# Controller_Sheet.net
KiCad netlist of a schematic drawn in Altium Designer
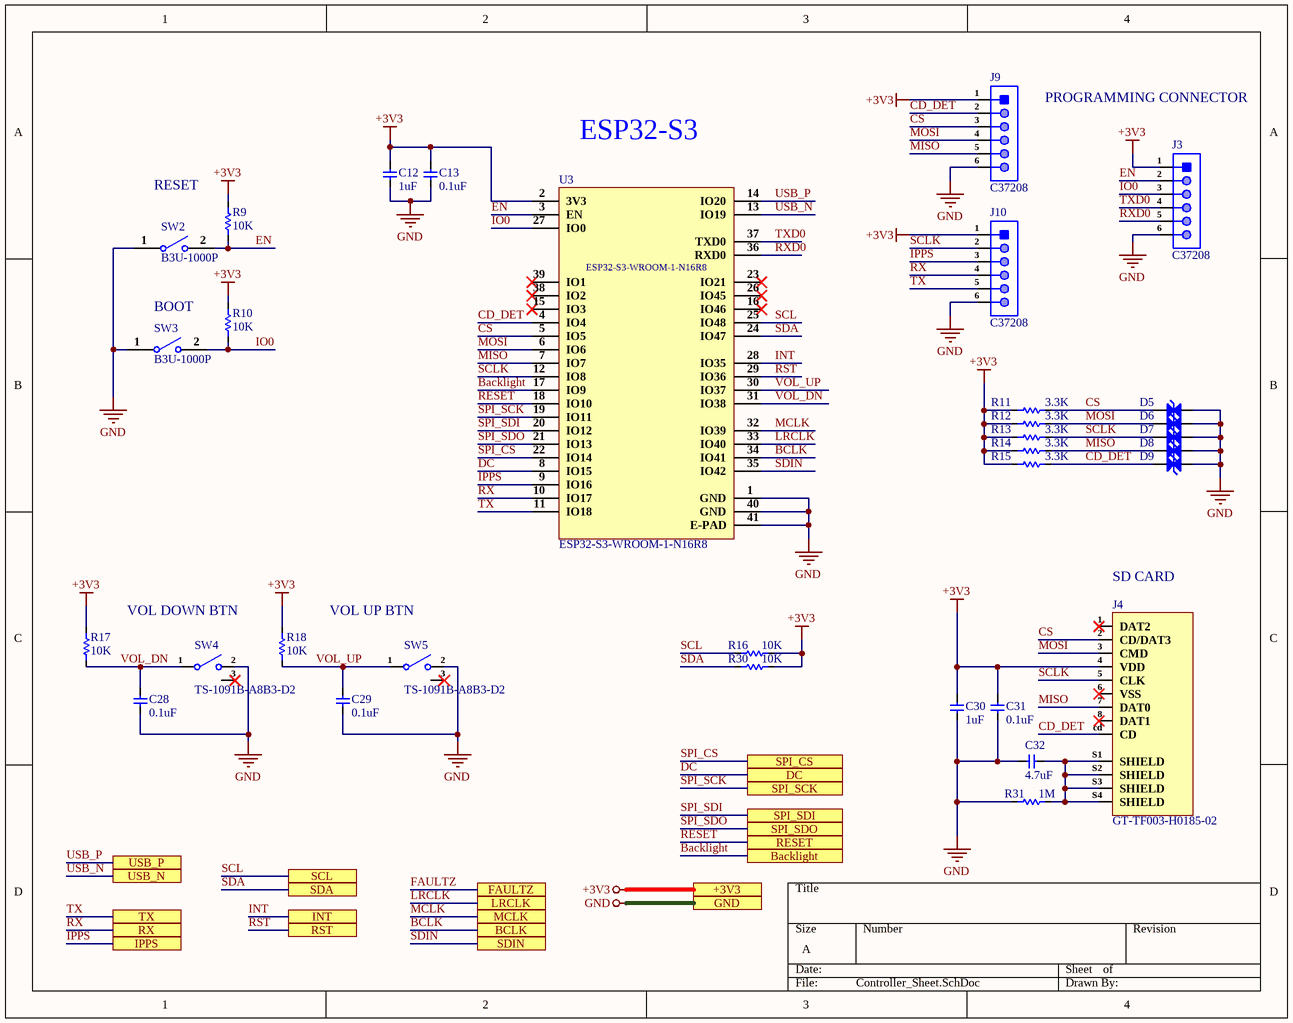
[diagram p0: Controller_Sheet.SchDoc]

(export (version "E")
  (design (tool "Eeschema 10.0.6"))
  (components
    (comp (ref "C12")
      (value "1uF")
      (footprint "Cap-0603")
      (description "CAP CER 1UF 25V X5R 0603")
      (fields
        (field (name "MANUFACTURER") "Yageo")
        (field (name "MANUFACTURER PART NUMBER") "CC0603KRX5R8BB105")
      )
      (libsource (lib "DigitalAzanClock") (part "CC0603KRX5R8BB105"))
    )
    (comp (ref "C13")
      (value "0.1uF")
      (footprint "Cap-0603")
      (description "CAP CER 0.1UF 100V X7R 0603")
      (fields
        (field (name "MANUFACTURER") "Yageo")
        (field (name "MANUFACTURER PART NUMBER") "CC0603KRX7R0BB104")
      )
      (libsource (lib "DigitalAzanClock") (part "CC0603KRX7R0BB104"))
    )
    (comp (ref "C28")
      (value "0.1uF")
      (footprint "Cap-0603")
      (description "CAP CER 0.1UF 100V X7R 0603")
      (fields
        (field (name "MANUFACTURER") "Yageo")
        (field (name "MANUFACTURER PART NUMBER") "CC0603KRX7R0BB104")
      )
      (libsource (lib "DigitalAzanClock") (part "CC0603KRX7R0BB104"))
    )
    (comp (ref "C29")
      (value "0.1uF")
      (footprint "Cap-0603")
      (description "CAP CER 0.1UF 100V X7R 0603")
      (fields
        (field (name "MANUFACTURER") "Yageo")
        (field (name "MANUFACTURER PART NUMBER") "CC0603KRX7R0BB104")
      )
      (libsource (lib "DigitalAzanClock") (part "CC0603KRX7R0BB104"))
    )
    (comp (ref "C30")
      (value "1uF")
      (footprint "Cap-0603")
      (description "CAP CER 1UF 25V X5R 0603")
      (fields
        (field (name "MANUFACTURER") "Yageo")
        (field (name "MANUFACTURER PART NUMBER") "CC0603KRX5R8BB105")
      )
      (libsource (lib "DigitalAzanClock") (part "CC0603KRX5R8BB105"))
    )
    (comp (ref "C31")
      (value "0.1uF")
      (footprint "Cap-0603")
      (description "CAP CER 0.1UF 100V X7R 0603")
      (fields
        (field (name "MANUFACTURER") "Yageo")
        (field (name "MANUFACTURER PART NUMBER") "CC0603KRX7R0BB104")
      )
      (libsource (lib "DigitalAzanClock") (part "CC0603KRX7R0BB104"))
    )
    (comp (ref "C32")
      (value "4.7uF")
      (footprint "Cap-0603")
      (description "50V 4.7nF X7R ±10% 0603 Multilayer Ceramic Capacitors MLCC - SMD/SMT ROHS")
      (fields
        (field (name "MANUFACTURER") "YAGEO")
        (field (name "MANUFACTURER PART NUMBER") "CC0603KRX7R9BB472")
      )
      (libsource (lib "DigitalAzanClock") (part "CC0603KRX7R9BB472"))
    )
    (comp (ref "D5")
      (value "ESD9X5VU")
      (footprint "DFN1006-2L_")
      (description "DFN1006-2 ESD Protection Devices ROHS")
      (fields (field (name "MANUFACTURER") "TECH PUBLIC") (field (name "LCSC PART NUMBER") "C2875160"))
      (libsource (lib "DigitalAzanClock") (part "ESD9X5VU"))
    )
    (comp (ref "D6")
      (value "ESD9X5VU")
      (footprint "DFN1006-2L_")
      (description "DFN1006-2 ESD Protection Devices ROHS")
      (fields (field (name "MANUFACTURER") "TECH PUBLIC") (field (name "LCSC PART NUMBER") "C2875160"))
      (libsource (lib "DigitalAzanClock") (part "ESD9X5VU"))
    )
    (comp (ref "D7")
      (value "ESD9X5VU")
      (footprint "DFN1006-2L_")
      (description "DFN1006-2 ESD Protection Devices ROHS")
      (fields (field (name "MANUFACTURER") "TECH PUBLIC") (field (name "LCSC PART NUMBER") "C2875160"))
      (libsource (lib "DigitalAzanClock") (part "ESD9X5VU"))
    )
    (comp (ref "D8")
      (value "ESD9X5VU")
      (footprint "DFN1006-2L_")
      (description "DFN1006-2 ESD Protection Devices ROHS")
      (fields (field (name "MANUFACTURER") "TECH PUBLIC") (field (name "LCSC PART NUMBER") "C2875160"))
      (libsource (lib "DigitalAzanClock") (part "ESD9X5VU"))
    )
    (comp (ref "D9")
      (value "ESD9X5VU")
      (footprint "DFN1006-2L_")
      (description "DFN1006-2 ESD Protection Devices ROHS")
      (fields (field (name "MANUFACTURER") "TECH PUBLIC") (field (name "LCSC PART NUMBER") "C2875160"))
      (libsource (lib "DigitalAzanClock") (part "ESD9X5VU"))
    )
    (comp (ref "J3")
      (value "C37208")
      (footprint "HDR1X6_")
      (description "Straight 1 6 2.54mm Black Brass Plugin,P=2.54mm Pin Headers ROHS")
      (fields (field (name "MANUFACTURER") "BOOMELEC"))
      (libsource (lib "DigitalAzanClock") (part "C37208"))
    )
    (comp (ref "J4")
      (value "GT-TF003-H0185-02")
      (footprint "GT-TF003-H0185-02")
      (fields (field (name "MANUFACTURER") "G-Switch") (field (name "LCSC PART NUMBER") "C5155564"))
      (libsource (lib "DigitalAzanClock") (part "GT-TF003-H0185-02"))
    )
    (comp (ref "J9")
      (value "C37208")
      (footprint "HDR1X6_")
      (description "Straight 1 6 2.54mm Black Brass Plugin,P=2.54mm Pin Headers ROHS")
      (fields (field (name "MANUFACTURER") "BOOMELEC"))
      (libsource (lib "DigitalAzanClock") (part "C37208"))
    )
    (comp (ref "J10")
      (value "C37208")
      (footprint "HDR1X6_")
      (description "Straight 1 6 2.54mm Black Brass Plugin,P=2.54mm Pin Headers ROHS")
      (fields (field (name "MANUFACTURER") "BOOMELEC"))
      (libsource (lib "DigitalAzanClock") (part "C37208"))
    )
    (comp (ref "R9")
      (value "10K")
      (footprint "Res-0603")
      (description "RES SMD 10K OHM 0.1% 1/10W 0603")
      (fields
        (field (name "MANUFACTURER") "Yageo")
        (field (name "MANUFACTURER PART NUMBER") "RT0603BRD0710KL")
      )
      (libsource (lib "DigitalAzanClock") (part "RT0603BRD0710KL"))
    )
    (comp (ref "R10")
      (value "10K")
      (footprint "Res-0603")
      (description "RES SMD 10K OHM 0.1% 1/10W 0603")
      (fields
        (field (name "MANUFACTURER") "Yageo")
        (field (name "MANUFACTURER PART NUMBER") "RT0603BRD0710KL")
      )
      (libsource (lib "DigitalAzanClock") (part "RT0603BRD0710KL"))
    )
    (comp (ref "R11")
      (value "3.3K")
      (footprint "Res-0603")
      (description "100mW Thick Film Resistors 75V ±100ppm/℃ ±1% 3.3kΩ 0603 Chip Resistor - Surface Mount ROHS")
      (fields
        (field (name "MANUFACTURER") "UNI-ROYAL(Uniroyal Elec)")
        (field (name "MANUFACTURER PART NUMBER") "0603WAF3301T5E")
      )
      (libsource (lib "DigitalAzanClock") (part "0603WAF3301T5E"))
    )
    (comp (ref "R12")
      (value "3.3K")
      (footprint "Res-0603")
      (description "100mW Thick Film Resistors 75V ±100ppm/℃ ±1% 3.3kΩ 0603 Chip Resistor - Surface Mount ROHS")
      (fields
        (field (name "MANUFACTURER") "UNI-ROYAL(Uniroyal Elec)")
        (field (name "MANUFACTURER PART NUMBER") "0603WAF3301T5E")
      )
      (libsource (lib "DigitalAzanClock") (part "0603WAF3301T5E"))
    )
    (comp (ref "R13")
      (value "3.3K")
      (footprint "Res-0603")
      (description "100mW Thick Film Resistors 75V ±100ppm/℃ ±1% 3.3kΩ 0603 Chip Resistor - Surface Mount ROHS")
      (fields
        (field (name "MANUFACTURER") "UNI-ROYAL(Uniroyal Elec)")
        (field (name "MANUFACTURER PART NUMBER") "0603WAF3301T5E")
      )
      (libsource (lib "DigitalAzanClock") (part "0603WAF3301T5E"))
    )
    (comp (ref "R14")
      (value "3.3K")
      (footprint "Res-0603")
      (description "100mW Thick Film Resistors 75V ±100ppm/℃ ±1% 3.3kΩ 0603 Chip Resistor - Surface Mount ROHS")
      (fields
        (field (name "MANUFACTURER") "UNI-ROYAL(Uniroyal Elec)")
        (field (name "MANUFACTURER PART NUMBER") "0603WAF3301T5E")
      )
      (libsource (lib "DigitalAzanClock") (part "0603WAF3301T5E"))
    )
    (comp (ref "R15")
      (value "3.3K")
      (footprint "Res-0603")
      (description "100mW Thick Film Resistors 75V ±100ppm/℃ ±1% 3.3kΩ 0603 Chip Resistor - Surface Mount ROHS")
      (fields
        (field (name "MANUFACTURER") "UNI-ROYAL(Uniroyal Elec)")
        (field (name "MANUFACTURER PART NUMBER") "0603WAF3301T5E")
      )
      (libsource (lib "DigitalAzanClock") (part "0603WAF3301T5E"))
    )
    (comp (ref "R16")
      (value "10K")
      (footprint "Res-0603")
      (description "RES SMD 10K OHM 0.1% 1/10W 0603")
      (fields
        (field (name "MANUFACTURER") "Yageo")
        (field (name "MANUFACTURER PART NUMBER") "RT0603BRD0710KL")
      )
      (libsource (lib "DigitalAzanClock") (part "RT0603BRD0710KL"))
    )
    (comp (ref "R17")
      (value "10K")
      (footprint "Res-0603")
      (description "RES SMD 10K OHM 0.1% 1/10W 0603")
      (fields
        (field (name "MANUFACTURER") "Yageo")
        (field (name "MANUFACTURER PART NUMBER") "RT0603BRD0710KL")
      )
      (libsource (lib "DigitalAzanClock") (part "RT0603BRD0710KL"))
    )
    (comp (ref "R18")
      (value "10K")
      (footprint "Res-0603")
      (description "RES SMD 10K OHM 0.1% 1/10W 0603")
      (fields
        (field (name "MANUFACTURER") "Yageo")
        (field (name "MANUFACTURER PART NUMBER") "RT0603BRD0710KL")
      )
      (libsource (lib "DigitalAzanClock") (part "RT0603BRD0710KL"))
    )
    (comp (ref "R30")
      (value "10K")
      (footprint "Res-0603")
      (description "RES SMD 10K OHM 0.1% 1/10W 0603")
      (fields
        (field (name "MANUFACTURER") "Yageo")
        (field (name "MANUFACTURER PART NUMBER") "RT0603BRD0710KL")
      )
      (libsource (lib "DigitalAzanClock") (part "RT0603BRD0710KL"))
    )
    (comp (ref "R31")
      (value "1M")
      (footprint "Res-0402")
      (description "RES SMD 1M OHM 5% 1/16W 0402")
      (fields
        (field (name "MANUFACTURER") "Yageo")
        (field (name "MANUFACTURER PART NUMBER") "AF0402JR-071ML")
      )
      (libsource (lib "DigitalAzanClock") (part "AF0402JR-071ML"))
    )
    (comp (ref "SW2")
      (value "B3U-1000P")
      (footprint "B3U-1000P")
      (description "SWITCH TACTILE SPST-NO 0.05A 12V")
      (fields (field (name "MANUFACTURER") "Omron") (field (name "LCSC PART NUMBER") "C231329"))
      (libsource (lib "DigitalAzanClock") (part "B3U-1000P"))
    )
    (comp (ref "SW3")
      (value "B3U-1000P")
      (footprint "B3U-1000P")
      (description "SWITCH TACTILE SPST-NO 0.05A 12V")
      (fields (field (name "MANUFACTURER") "Omron") (field (name "LCSC PART NUMBER") "C231329"))
      (libsource (lib "DigitalAzanClock") (part "B3U-1000P"))
    )
    (comp (ref "SW4")
      (value "TS-1091B-A8B3-D2")
      (footprint "TS-1091B-A8B3-D2")
      (description "NO Lying SPST 250gf@±30gf Plugin Tactile Switches ROHS")
      (fields (field (name "MANUFACTURER") "Yuandi") (field (name "LCSC PART NUMBER") "C557914"))
      (libsource (lib "DigitalAzanClock") (part "TS-1091B-A8B3-D2"))
    )
    (comp (ref "SW5")
      (value "TS-1091B-A8B3-D2")
      (footprint "TS-1091B-A8B3-D2")
      (description "NO Lying SPST 250gf@±30gf Plugin Tactile Switches ROHS")
      (fields (field (name "MANUFACTURER") "Yuandi") (field (name "LCSC PART NUMBER") "C557914"))
      (libsource (lib "DigitalAzanClock") (part "TS-1091B-A8B3-D2"))
    )
    (comp (ref "U3")
      (value "ESP32-S3-WROOM-1-N16R8")
      (footprint "41-SMD Module")
      (description "ESP32-S3 chip 2.4GHz SMD,18x25.5mm WiFi Modules ROHS")
      (fields
        (field (name "MANUFACTURER") "Expressif System")
        (field (name "MANUFACTURER PART NUMBER") "ESP32-S3-WROOM-1-N8")
      )
      (libsource (lib "DigitalAzanClock") (part "ESP32-S3-WROOM-1-N16R8"))
    )
  )
  (nets
    (net (code "1") (name "+3V3") (class "Default")
      (node (ref "C12") (pin "2") (pinfunction "2_2") (pintype "passive"))
      (node (ref "C13") (pin "2") (pinfunction "2_2") (pintype "passive"))
      (node (ref "C30") (pin "2") (pinfunction "2_2") (pintype "passive"))
      (node (ref "C31") (pin "2") (pinfunction "2_2") (pintype "passive"))
      (node (ref "J10") (pin "1") (pinfunction "1_1") (pintype "passive"))
      (node (ref "J3") (pin "1") (pinfunction "1_1") (pintype "passive"))
      (node (ref "J4") (pin "4") (pinfunction "VDD_4") (pintype "passive"))
      (node (ref "J9") (pin "1") (pinfunction "1_1") (pintype "passive"))
      (node (ref "R10") (pin "2") (pinfunction "2_2") (pintype "passive"))
      (node (ref "R11") (pin "1") (pinfunction "1_1") (pintype "passive"))
      (node (ref "R12") (pin "1") (pinfunction "1_1") (pintype "passive"))
      (node (ref "R13") (pin "1") (pinfunction "1_1") (pintype "passive"))
      (node (ref "R14") (pin "1") (pinfunction "1_1") (pintype "passive"))
      (node (ref "R15") (pin "1") (pinfunction "1_1") (pintype "passive"))
      (node (ref "R16") (pin "1") (pinfunction "1_1") (pintype "passive"))
      (node (ref "R17") (pin "2") (pinfunction "2_2") (pintype "passive"))
      (node (ref "R18") (pin "2") (pinfunction "2_2") (pintype "passive"))
      (node (ref "R30") (pin "1") (pinfunction "1_1") (pintype "passive"))
      (node (ref "R9") (pin "2") (pinfunction "2_2") (pintype "passive"))
      (node (ref "U3") (pin "2") (pinfunction "3V3_2") (pintype "passive"))
    )
    (net (code "2") (name "/BCLK") (class "Default")
      (node (ref "U3") (pin "34") (pinfunction "IO41_34") (pintype "passive"))
    )
    (net (code "3") (name "/Backlight") (class "Default")
      (node (ref "U3") (pin "17") (pinfunction "IO9_17") (pintype "passive"))
    )
    (net (code "4") (name "/CD_DET") (class "Default")
      (node (ref "D9") (pin "1") (pinfunction "A_1") (pintype "passive"))
      (node (ref "J4") (pin "cd") (pinfunction "CD_cd") (pintype "passive"))
      (node (ref "J9") (pin "2") (pinfunction "2_2") (pintype "passive"))
      (node (ref "R15") (pin "2") (pinfunction "2_2") (pintype "passive"))
      (node (ref "U3") (pin "4") (pinfunction "IO4_4") (pintype "passive"))
    )
    (net (code "5") (name "/CS") (class "Default")
      (node (ref "D5") (pin "1") (pinfunction "A_1") (pintype "passive"))
      (node (ref "J4") (pin "2") (pinfunction "CD/DAT3_2") (pintype "passive"))
      (node (ref "J9") (pin "3") (pinfunction "3_3") (pintype "passive"))
      (node (ref "R11") (pin "2") (pinfunction "2_2") (pintype "passive"))
      (node (ref "U3") (pin "5") (pinfunction "IO5_5") (pintype "passive"))
    )
    (net (code "6") (name "/DC") (class "Default")
      (node (ref "U3") (pin "8") (pinfunction "IO15_8") (pintype "passive"))
    )
    (net (code "7") (name "/EN") (class "Default")
      (node (ref "J3") (pin "2") (pinfunction "2_2") (pintype "passive"))
      (node (ref "R9") (pin "1") (pinfunction "1_1") (pintype "passive"))
      (node (ref "SW2") (pin "2") (pinfunction "2_2") (pintype "passive"))
      (node (ref "U3") (pin "3") (pinfunction "EN_3") (pintype "passive"))
    )
    (net (code "9") (name "/INT") (class "Default")
      (node (ref "U3") (pin "28") (pinfunction "IO35_28") (pintype "passive"))
    )
    (net (code "10") (name "/IO0") (class "Default")
      (node (ref "J3") (pin "3") (pinfunction "3_3") (pintype "passive"))
      (node (ref "R10") (pin "1") (pinfunction "1_1") (pintype "passive"))
      (node (ref "SW3") (pin "2") (pinfunction "2_2") (pintype "passive"))
      (node (ref "U3") (pin "27") (pinfunction "IO0_27") (pintype "passive"))
    )
    (net (code "11") (name "/IPPS") (class "Default")
      (node (ref "J10") (pin "3") (pinfunction "3_3") (pintype "passive"))
      (node (ref "U3") (pin "9") (pinfunction "IO16_9") (pintype "passive"))
    )
    (net (code "12") (name "/LRCLK") (class "Default")
      (node (ref "U3") (pin "33") (pinfunction "IO40_33") (pintype "passive"))
    )
    (net (code "13") (name "/MCLK") (class "Default")
      (node (ref "U3") (pin "32") (pinfunction "IO39_32") (pintype "passive"))
    )
    (net (code "14") (name "/MISO") (class "Default")
      (node (ref "D8") (pin "1") (pinfunction "A_1") (pintype "passive"))
      (node (ref "J4") (pin "7") (pinfunction "DAT0_7") (pintype "passive"))
      (node (ref "J9") (pin "5") (pinfunction "5_5") (pintype "passive"))
      (node (ref "R14") (pin "2") (pinfunction "2_2") (pintype "passive"))
      (node (ref "U3") (pin "7") (pinfunction "IO7_7") (pintype "passive"))
    )
    (net (code "15") (name "/MOSI") (class "Default")
      (node (ref "D6") (pin "1") (pinfunction "A_1") (pintype "passive"))
      (node (ref "J4") (pin "3") (pinfunction "CMD_3") (pintype "passive"))
      (node (ref "J9") (pin "4") (pinfunction "4_4") (pintype "passive"))
      (node (ref "R12") (pin "2") (pinfunction "2_2") (pintype "passive"))
      (node (ref "U3") (pin "6") (pinfunction "IO6_6") (pintype "passive"))
    )
    (net (code "16") (name "/RESET") (class "Default")
      (node (ref "U3") (pin "18") (pinfunction "IO10_18") (pintype "passive"))
    )
    (net (code "17") (name "/RST") (class "Default")
      (node (ref "U3") (pin "29") (pinfunction "IO36_29") (pintype "passive"))
    )
    (net (code "18") (name "/RX") (class "Default")
      (node (ref "J10") (pin "4") (pinfunction "4_4") (pintype "passive"))
      (node (ref "U3") (pin "10") (pinfunction "IO17_10") (pintype "passive"))
    )
    (net (code "19") (name "/RXD0") (class "Default")
      (node (ref "J3") (pin "5") (pinfunction "5_5") (pintype "passive"))
      (node (ref "U3") (pin "36") (pinfunction "RXD0_36") (pintype "passive"))
    )
    (net (code "20") (name "/SCL") (class "Default")
      (node (ref "R16") (pin "2") (pinfunction "2_2") (pintype "passive"))
      (node (ref "U3") (pin "25") (pinfunction "IO48_25") (pintype "passive"))
    )
    (net (code "21") (name "/SCLK") (class "Default")
      (node (ref "D7") (pin "1") (pinfunction "A_1") (pintype "passive"))
      (node (ref "J10") (pin "2") (pinfunction "2_2") (pintype "passive"))
      (node (ref "J4") (pin "5") (pinfunction "CLK_5") (pintype "passive"))
      (node (ref "R13") (pin "2") (pinfunction "2_2") (pintype "passive"))
      (node (ref "U3") (pin "12") (pinfunction "IO8_12") (pintype "passive"))
    )
    (net (code "22") (name "/SDA") (class "Default")
      (node (ref "R30") (pin "2") (pinfunction "2_2") (pintype "passive"))
      (node (ref "U3") (pin "24") (pinfunction "IO47_24") (pintype "passive"))
    )
    (net (code "23") (name "/SDIN") (class "Default")
      (node (ref "U3") (pin "35") (pinfunction "IO42_35") (pintype "passive"))
    )
    (net (code "24") (name "/SPI_CS") (class "Default")
      (node (ref "U3") (pin "22") (pinfunction "IO14_22") (pintype "passive"))
    )
    (net (code "25") (name "/SPI_SCK") (class "Default")
      (node (ref "U3") (pin "19") (pinfunction "IO11_19") (pintype "passive"))
    )
    (net (code "26") (name "/SPI_SDI") (class "Default")
      (node (ref "U3") (pin "20") (pinfunction "IO12_20") (pintype "passive"))
    )
    (net (code "27") (name "/SPI_SDO") (class "Default")
      (node (ref "U3") (pin "21") (pinfunction "IO13_21") (pintype "passive"))
    )
    (net (code "28") (name "/TX") (class "Default")
      (node (ref "J10") (pin "5") (pinfunction "5_5") (pintype "passive"))
      (node (ref "U3") (pin "11") (pinfunction "IO18_11") (pintype "passive"))
    )
    (net (code "29") (name "/TXD0") (class "Default")
      (node (ref "J3") (pin "4") (pinfunction "4_4") (pintype "passive"))
      (node (ref "U3") (pin "37") (pinfunction "TXD0_37") (pintype "passive"))
    )
    (net (code "30") (name "/USB_N") (class "Default")
      (node (ref "U3") (pin "13") (pinfunction "IO19_13") (pintype "passive"))
    )
    (net (code "31") (name "/USB_P") (class "Default")
      (node (ref "U3") (pin "14") (pinfunction "IO20_14") (pintype "passive"))
    )
    (net (code "32") (name "/VOL_DN") (class "Default")
      (node (ref "C28") (pin "2") (pinfunction "2_2") (pintype "passive"))
      (node (ref "R17") (pin "1") (pinfunction "1_1") (pintype "passive"))
      (node (ref "SW4") (pin "1") (pinfunction "1_1") (pintype "passive"))
      (node (ref "U3") (pin "31") (pinfunction "IO38_31") (pintype "passive"))
    )
    (net (code "33") (name "/VOL_UP") (class "Default")
      (node (ref "C29") (pin "2") (pinfunction "2_2") (pintype "passive"))
      (node (ref "R18") (pin "1") (pinfunction "1_1") (pintype "passive"))
      (node (ref "SW5") (pin "1") (pinfunction "1_1") (pintype "passive"))
      (node (ref "U3") (pin "30") (pinfunction "IO37_30") (pintype "passive"))
    )
    (net (code "34") (name "GND") (class "Default")
      (node (ref "C12") (pin "1") (pinfunction "1_1") (pintype "passive"))
      (node (ref "C13") (pin "1") (pinfunction "1_1") (pintype "passive"))
      (node (ref "C28") (pin "1") (pinfunction "1_1") (pintype "passive"))
      (node (ref "C29") (pin "1") (pinfunction "1_1") (pintype "passive"))
      (node (ref "C30") (pin "1") (pinfunction "1_1") (pintype "passive"))
      (node (ref "C31") (pin "1") (pinfunction "1_1") (pintype "passive"))
      (node (ref "C32") (pin "2") (pinfunction "2_2") (pintype "passive"))
      (node (ref "D5") (pin "2") (pinfunction "A_2") (pintype "passive"))
      (node (ref "D6") (pin "2") (pinfunction "A_2") (pintype "passive"))
      (node (ref "D7") (pin "2") (pinfunction "A_2") (pintype "passive"))
      (node (ref "D8") (pin "2") (pinfunction "A_2") (pintype "passive"))
      (node (ref "D9") (pin "2") (pinfunction "A_2") (pintype "passive"))
      (node (ref "J10") (pin "6") (pinfunction "6_6") (pintype "passive"))
      (node (ref "J3") (pin "6") (pinfunction "6_6") (pintype "passive"))
      (node (ref "J9") (pin "6") (pinfunction "6_6") (pintype "passive"))
      (node (ref "R31") (pin "2") (pinfunction "2_2") (pintype "passive"))
      (node (ref "SW2") (pin "1") (pinfunction "1_1") (pintype "passive"))
      (node (ref "SW3") (pin "1") (pinfunction "1_1") (pintype "passive"))
      (node (ref "SW4") (pin "2") (pinfunction "2_2") (pintype "passive"))
      (node (ref "SW5") (pin "2") (pinfunction "2_2") (pintype "passive"))
      (node (ref "U3") (pin "1") (pinfunction "GND_1") (pintype "passive"))
      (node (ref "U3") (pin "40") (pinfunction "GND_40") (pintype "passive"))
      (node (ref "U3") (pin "41") (pinfunction "E-PAD_41") (pintype "passive"))
    )
    (net (code "35") (name "Net-(C32-Pad1)") (class "Default")
      (node (ref "C32") (pin "1") (pinfunction "1_1") (pintype "passive"))
      (node (ref "J4") (pin "S1") (pinfunction "SHIELD_S1") (pintype "passive"))
      (node (ref "J4") (pin "S2") (pinfunction "SHIELD_S2") (pintype "passive"))
      (node (ref "J4") (pin "S3") (pinfunction "SHIELD_S3") (pintype "passive"))
      (node (ref "J4") (pin "S4") (pinfunction "SHIELD_S4") (pintype "passive"))
      (node (ref "R31") (pin "1") (pinfunction "1_1") (pintype "passive"))
    )
    (net (code "36") (name "unconnected-(J4-DAT1-Pad8)") (class "Default")
      (node (ref "J4") (pin "8") (pinfunction "DAT1_8") (pintype "passive+no_connect"))
    )
    (net (code "37") (name "unconnected-(J4-DAT2-Pad1)") (class "Default")
      (node (ref "J4") (pin "1") (pinfunction "DAT2_1") (pintype "passive+no_connect"))
    )
    (net (code "38") (name "unconnected-(J4-VSS-Pad6)") (class "Default")
      (node (ref "J4") (pin "6") (pinfunction "VSS_6") (pintype "passive+no_connect"))
    )
    (net (code "39") (name "unconnected-(SW4-Pad3)") (class "Default")
      (node (ref "SW4") (pin "3") (pinfunction "3_3") (pintype "passive+no_connect"))
    )
    (net (code "40") (name "unconnected-(SW5-Pad3)") (class "Default")
      (node (ref "SW5") (pin "3") (pinfunction "3_3") (pintype "passive+no_connect"))
    )
    (net (code "41") (name "unconnected-(U3-IO1-Pad39)") (class "Default")
      (node (ref "U3") (pin "39") (pinfunction "IO1_39") (pintype "passive+no_connect"))
    )
    (net (code "42") (name "unconnected-(U3-IO2-Pad38)") (class "Default")
      (node (ref "U3") (pin "38") (pinfunction "IO2_38") (pintype "passive+no_connect"))
    )
    (net (code "43") (name "unconnected-(U3-IO3-Pad15)") (class "Default")
      (node (ref "U3") (pin "15") (pinfunction "IO3_15") (pintype "passive+no_connect"))
    )
    (net (code "44") (name "unconnected-(U3-IO21-Pad23)") (class "Default")
      (node (ref "U3") (pin "23") (pinfunction "IO21_23") (pintype "passive+no_connect"))
    )
    (net (code "45") (name "unconnected-(U3-IO45-Pad26)") (class "Default")
      (node (ref "U3") (pin "26") (pinfunction "IO45_26") (pintype "passive+no_connect"))
    )
    (net (code "46") (name "unconnected-(U3-IO46-Pad16)") (class "Default")
      (node (ref "U3") (pin "16") (pinfunction "IO46_16") (pintype "passive+no_connect"))
    )
  )
)
